# i2c_pressure.net
KiCad netlist of a schematic drawn in EAGLE
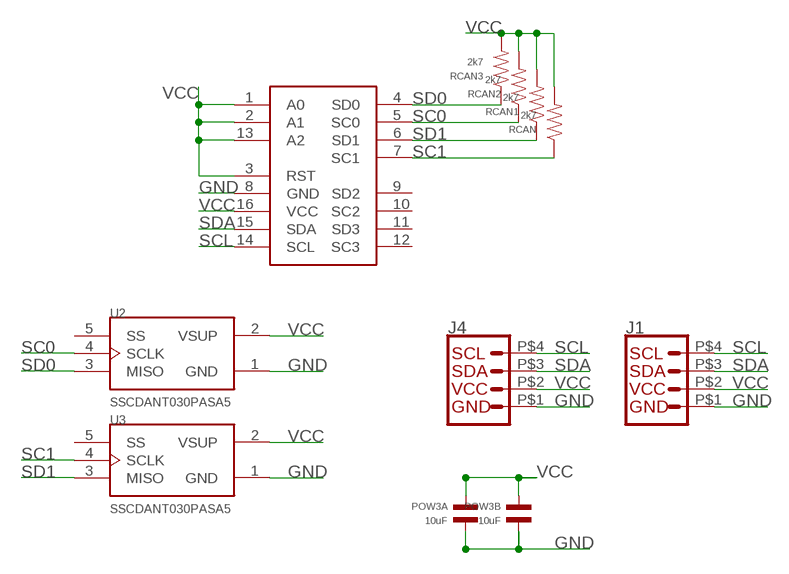
[diagram p0: schematic, sheet 1]

(export (version "E")
  (design (tool "Eeschema 10.0.6"))
  (components
    (comp (ref "J1")
      (value "Vertical Qwiic Connector")
      (footprint "eagle-import:JST04_1MM_HOLES")
      (libsource (lib "eagle-import") (part "QWIIC_CONNECTORJST04_1MM_HOLE"))
    )
    (comp (ref "J4")
      (value "Vertical Qwiic Connector")
      (footprint "eagle-import:JST04_1MM_HOLES")
      (libsource (lib "eagle-import") (part "QWIIC_CONNECTORJST04_1MM_HOLE"))
    )
    (comp (ref "POW3A")
      (value "10uF")
      (footprint "eagle-import:C0603")
      (libsource (lib "eagle-import") (part "CAPACITOR_NP_0603"))
    )
    (comp (ref "POW3B")
      (value "10uF")
      (footprint "eagle-import:C0603")
      (libsource (lib "eagle-import") (part "CAPACITOR_NP_0603"))
    )
    (comp (ref "RCAN")
      (value "2k7")
      (footprint "eagle-import:R0603")
      (libsource (lib "eagle-import") (part "RESISTOR_0603"))
    )
    (comp (ref "RCAN1")
      (value "2k7")
      (footprint "eagle-import:R0603")
      (libsource (lib "eagle-import") (part "RESISTOR_0603"))
    )
    (comp (ref "RCAN2")
      (value "2k7")
      (footprint "eagle-import:R0603")
      (libsource (lib "eagle-import") (part "RESISTOR_0603"))
    )
    (comp (ref "RCAN3")
      (value "2k7")
      (footprint "eagle-import:R0603")
      (libsource (lib "eagle-import") (part "RESISTOR_0603"))
    )
    (comp (ref "U$1")
      (value "TCA9546ATSSOP16")
      (footprint "eagle-import:TSSOP16")
      (libsource (lib "eagle-import") (part "TCA9546ATSSOP16"))
    )
    (comp (ref "U2")
      (value "SSCDANT030PASA5")
      (footprint "eagle-import:XDCR_SSCDANT030PASA5")
      (fields (field (name "MF") "Honeywell Sensing"))
      (libsource (lib "eagle-import") (part "SSCDANT030PASA5"))
    )
    (comp (ref "U3")
      (value "SSCDANT030PASA5")
      (footprint "eagle-import:XDCR_SSCDANT030PASA5")
      (fields (field (name "MF") "Honeywell Sensing"))
      (libsource (lib "eagle-import") (part "SSCDANT030PASA5"))
    )
  )
  (nets
    (net (code "1") (name "/GND") (class "Default")
      (node (ref "J1") (pin "P$1") (pinfunction "1_P$1") (pintype "power_in"))
      (node (ref "J4") (pin "P$1") (pinfunction "1_P$1") (pintype "power_in"))
      (node (ref "POW3A") (pin "P$2") (pinfunction "P$2_P$2") (pintype "passive"))
      (node (ref "POW3B") (pin "P$2") (pinfunction "P$2_P$2") (pintype "passive"))
      (node (ref "U$1") (pin "8") (pinfunction "GND_8") (pintype "bidirectional"))
      (node (ref "U2") (pin "1") (pinfunction "GND_1") (pintype "power_in"))
      (node (ref "U3") (pin "1") (pinfunction "GND_1") (pintype "power_in"))
    )
    (net (code "2") (name "/SC0") (class "Default")
      (node (ref "RCAN2") (pin "P$1") (pinfunction "P$1_P$1") (pintype "passive"))
      (node (ref "U$1") (pin "5") (pinfunction "SC0_5") (pintype "bidirectional"))
      (node (ref "U2") (pin "4") (pinfunction "SCLK_4") (pintype "input"))
    )
    (net (code "3") (name "/SC1") (class "Default")
      (node (ref "RCAN") (pin "P$1") (pinfunction "P$1_P$1") (pintype "passive"))
      (node (ref "U$1") (pin "7") (pinfunction "SC1_7") (pintype "bidirectional"))
      (node (ref "U3") (pin "4") (pinfunction "SCLK_4") (pintype "input"))
    )
    (net (code "4") (name "/SCL") (class "Default")
      (node (ref "J1") (pin "P$4") (pinfunction "4_P$4") (pintype "passive"))
      (node (ref "J4") (pin "P$4") (pinfunction "4_P$4") (pintype "passive"))
      (node (ref "U$1") (pin "14") (pinfunction "SCL_14") (pintype "bidirectional"))
    )
    (net (code "5") (name "/SD0") (class "Default")
      (node (ref "RCAN3") (pin "P$1") (pinfunction "P$1_P$1") (pintype "passive"))
      (node (ref "U$1") (pin "4") (pinfunction "SD0_4") (pintype "bidirectional"))
      (node (ref "U2") (pin "3") (pinfunction "MISO_3") (pintype "bidirectional"))
    )
    (net (code "6") (name "/SD1") (class "Default")
      (node (ref "RCAN1") (pin "P$1") (pinfunction "P$1_P$1") (pintype "passive"))
      (node (ref "U$1") (pin "6") (pinfunction "SD1_6") (pintype "bidirectional"))
      (node (ref "U3") (pin "3") (pinfunction "MISO_3") (pintype "bidirectional"))
    )
    (net (code "7") (name "/SDA") (class "Default")
      (node (ref "J1") (pin "P$3") (pinfunction "3_P$3") (pintype "passive"))
      (node (ref "J4") (pin "P$3") (pinfunction "3_P$3") (pintype "passive"))
      (node (ref "U$1") (pin "15") (pinfunction "SDA_15") (pintype "bidirectional"))
    )
    (net (code "8") (name "/VCC") (class "Default")
      (node (ref "J1") (pin "P$2") (pinfunction "2_P$2") (pintype "power_in"))
      (node (ref "J4") (pin "P$2") (pinfunction "2_P$2") (pintype "power_in"))
      (node (ref "POW3A") (pin "P$1") (pinfunction "P$1_P$1") (pintype "passive"))
      (node (ref "POW3B") (pin "P$1") (pinfunction "P$1_P$1") (pintype "passive"))
      (node (ref "RCAN") (pin "P$2") (pinfunction "P$2_P$2") (pintype "passive"))
      (node (ref "RCAN1") (pin "P$2") (pinfunction "P$2_P$2") (pintype "passive"))
      (node (ref "RCAN2") (pin "P$2") (pinfunction "P$2_P$2") (pintype "passive"))
      (node (ref "RCAN3") (pin "P$2") (pinfunction "P$2_P$2") (pintype "passive"))
      (node (ref "U$1") (pin "1") (pinfunction "A0_1") (pintype "bidirectional"))
      (node (ref "U$1") (pin "13") (pinfunction "A2_13") (pintype "bidirectional"))
      (node (ref "U$1") (pin "16") (pinfunction "VCC_16") (pintype "bidirectional"))
      (node (ref "U$1") (pin "2") (pinfunction "A1_2") (pintype "bidirectional"))
      (node (ref "U$1") (pin "3") (pinfunction "RST_3") (pintype "bidirectional"))
      (node (ref "U2") (pin "2") (pinfunction "VSUP_2") (pintype "power_in"))
      (node (ref "U3") (pin "2") (pinfunction "VSUP_2") (pintype "power_in"))
    )
    (net (code "9") (name "unconnected-(U$1-SC2-Pad10)") (class "Default")
      (node (ref "U$1") (pin "10") (pinfunction "SC2_10") (pintype "bidirectional"))
    )
    (net (code "10") (name "unconnected-(U$1-SC3-Pad12)") (class "Default")
      (node (ref "U$1") (pin "12") (pinfunction "SC3_12") (pintype "bidirectional"))
    )
    (net (code "11") (name "unconnected-(U$1-SD2-Pad9)") (class "Default")
      (node (ref "U$1") (pin "9") (pinfunction "SD2_9") (pintype "bidirectional"))
    )
    (net (code "12") (name "unconnected-(U$1-SD3-Pad11)") (class "Default")
      (node (ref "U$1") (pin "11") (pinfunction "SD3_11") (pintype "bidirectional"))
    )
    (net (code "13") (name "unconnected-(U2-SS-Pad5)") (class "Default")
      (node (ref "U2") (pin "5") (pinfunction "SS_5") (pintype "input"))
    )
    (net (code "14") (name "unconnected-(U3-SS-Pad5)") (class "Default")
      (node (ref "U3") (pin "5") (pinfunction "SS_5") (pintype "input"))
    )
  )
)
